# Sheet2.net
KiCad netlist of a schematic drawn in Altium Designer
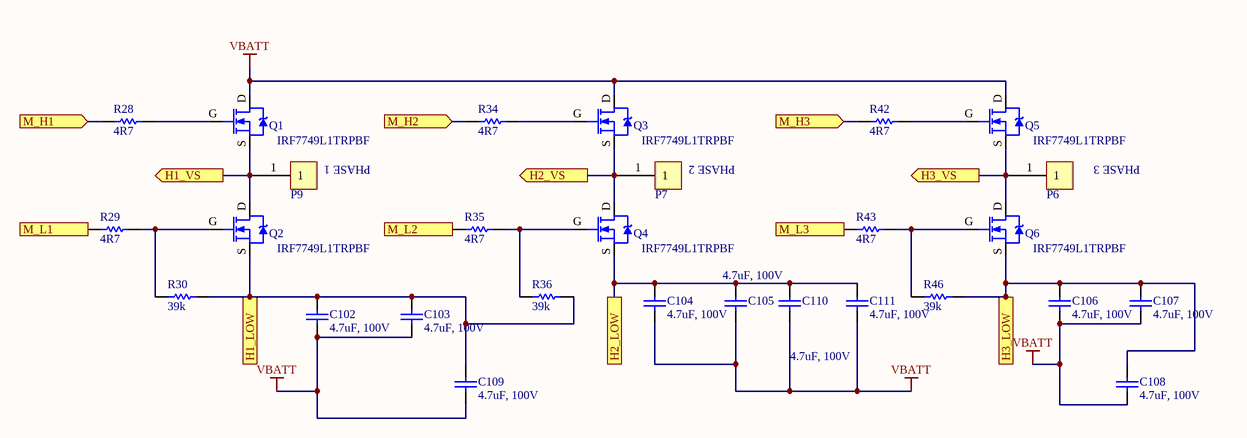
[diagram p0: Sheet2.SchDoc]

(export (version "E")
  (design (tool "Eeschema 10.0.6"))
  (components
    (comp (ref "C102")
      (value "4.7uF, 100V")
      (footprint "SMD-1206 Capacitor")
      (description "4.7µF 100V Ceramic Capacitor X7S 1206")
      (fields
        (field (name "MANUFACTURER PART NUMBER") "12061Z475MAT2A")
        (field (name "MANUFACTURER") "AVX Corporation")
      )
      (libsource (lib "Master Data Link") (part "CAP"))
    )
    (comp (ref "C103")
      (value "4.7uF, 100V")
      (footprint "SMD-1206 Capacitor")
      (description "4.7µF 100V Ceramic Capacitor X7S 1206")
      (fields
        (field (name "MANUFACTURER PART NUMBER") "12061Z475MAT2A")
        (field (name "MANUFACTURER") "AVX Corporation")
      )
      (libsource (lib "Master Data Link") (part "CAP"))
    )
    (comp (ref "C104")
      (value "4.7uF, 100V")
      (footprint "SMD-1206 Capacitor")
      (description "4.7µF 100V Ceramic Capacitor X7S 1206")
      (fields
        (field (name "MANUFACTURER PART NUMBER") "12061Z475MAT2A")
        (field (name "MANUFACTURER") "AVX Corporation")
      )
      (libsource (lib "Master Data Link") (part "CAP"))
    )
    (comp (ref "C105")
      (value "4.7uF, 100V")
      (footprint "SMD-1206 Capacitor")
      (description "4.7µF 100V Ceramic Capacitor X7S 1206")
      (fields
        (field (name "MANUFACTURER PART NUMBER") "12061Z475MAT2A")
        (field (name "MANUFACTURER") "AVX Corporation")
      )
      (libsource (lib "Master Data Link") (part "CAP"))
    )
    (comp (ref "C106")
      (value "4.7uF, 100V")
      (footprint "SMD-1206 Capacitor")
      (description "4.7µF 100V Ceramic Capacitor X7S 1206")
      (fields
        (field (name "MANUFACTURER PART NUMBER") "12061Z475MAT2A")
        (field (name "MANUFACTURER") "AVX Corporation")
      )
      (libsource (lib "Master Data Link") (part "CAP"))
    )
    (comp (ref "C107")
      (value "4.7uF, 100V")
      (footprint "SMD-1206 Capacitor")
      (description "4.7µF 100V Ceramic Capacitor X7S 1206")
      (fields
        (field (name "MANUFACTURER PART NUMBER") "12061Z475MAT2A")
        (field (name "MANUFACTURER") "AVX Corporation")
      )
      (libsource (lib "Master Data Link") (part "CAP"))
    )
    (comp (ref "C108")
      (value "4.7uF, 100V")
      (footprint "SMD-1206 Capacitor")
      (description "4.7µF 100V Ceramic Capacitor X7S 1206")
      (fields
        (field (name "MANUFACTURER PART NUMBER") "12061Z475MAT2A")
        (field (name "MANUFACTURER") "AVX Corporation")
      )
      (libsource (lib "Master Data Link") (part "CAP"))
    )
    (comp (ref "C109")
      (value "4.7uF, 100V")
      (footprint "SMD-1206 Capacitor")
      (description "4.7µF 100V Ceramic Capacitor X7S 1206")
      (fields
        (field (name "MANUFACTURER PART NUMBER") "12061Z475MAT2A")
        (field (name "MANUFACTURER") "AVX Corporation")
      )
      (libsource (lib "Master Data Link") (part "CAP"))
    )
    (comp (ref "C110")
      (value "4.7uF, 100V")
      (footprint "SMD-1206 Capacitor")
      (description "4.7µF 100V Ceramic Capacitor X7S 1206")
      (fields
        (field (name "MANUFACTURER PART NUMBER") "12061Z475MAT2A")
        (field (name "MANUFACTURER") "AVX Corporation")
      )
      (libsource (lib "Master Data Link") (part "CAP"))
    )
    (comp (ref "C111")
      (value "4.7uF, 100V")
      (footprint "SMD-1206 Capacitor")
      (description "4.7µF 100V Ceramic Capacitor X7S 1206")
      (fields
        (field (name "MANUFACTURER PART NUMBER") "12061Z475MAT2A")
        (field (name "MANUFACTURER") "AVX Corporation")
      )
      (libsource (lib "Master Data Link") (part "CAP"))
    )
    (comp (ref "P6")
      (value "-")
      (footprint "PAD1")
      (description "SMD Power landing")
      (libsource (lib "Master Data Link") (part "CON1"))
    )
    (comp (ref "P7")
      (value "-")
      (footprint "PAD1")
      (description "SMD Power landing")
      (libsource (lib "Master Data Link") (part "CON1"))
    )
    (comp (ref "P9")
      (value "-")
      (footprint "PAD1")
      (description "SMD Power landing")
      (libsource (lib "Master Data Link") (part "CON1"))
    )
    (comp (ref "Q1")
      (value "MOSFET_N")
      (footprint "DIRECTFET_1")
      (description "MOSFET N-CH 60V 200A DIRECTFETL8")
      (fields
        (field (name "MANUFACTURER PART NUMBER") "IRF7749L1TRPBF")
        (field (name "MANUFACTURER") "Infineon Technologies Americas Corp")
      )
      (libsource (lib "Master Data Link") (part "MOSFET_N"))
    )
    (comp (ref "Q2")
      (value "MOSFET_N")
      (footprint "DIRECTFET_1")
      (description "MOSFET N-CH 60V 200A DIRECTFETL8")
      (fields
        (field (name "MANUFACTURER PART NUMBER") "IRF7749L1TRPBF")
        (field (name "MANUFACTURER") "Infineon Technologies Americas Corp")
      )
      (libsource (lib "Master Data Link") (part "MOSFET_N"))
    )
    (comp (ref "Q3")
      (value "MOSFET_N")
      (footprint "DIRECTFET_1")
      (description "MOSFET N-CH 60V 200A DIRECTFETL8")
      (fields
        (field (name "MANUFACTURER PART NUMBER") "IRF7749L1TRPBF")
        (field (name "MANUFACTURER") "Infineon Technologies Americas Corp")
      )
      (libsource (lib "Master Data Link") (part "MOSFET_N"))
    )
    (comp (ref "Q4")
      (value "MOSFET_N")
      (footprint "DIRECTFET_1")
      (description "MOSFET N-CH 60V 200A DIRECTFETL8")
      (fields
        (field (name "MANUFACTURER PART NUMBER") "IRF7749L1TRPBF")
        (field (name "MANUFACTURER") "Infineon Technologies Americas Corp")
      )
      (libsource (lib "Master Data Link") (part "MOSFET_N"))
    )
    (comp (ref "Q5")
      (value "MOSFET_N")
      (footprint "DIRECTFET_1")
      (description "MOSFET N-CH 60V 200A DIRECTFETL8")
      (fields
        (field (name "MANUFACTURER PART NUMBER") "IRF7749L1TRPBF")
        (field (name "MANUFACTURER") "Infineon Technologies Americas Corp")
      )
      (libsource (lib "Master Data Link") (part "MOSFET_N"))
    )
    (comp (ref "Q6")
      (value "MOSFET_N")
      (footprint "DIRECTFET_1")
      (description "MOSFET N-CH 60V 200A DIRECTFETL8")
      (fields
        (field (name "MANUFACTURER PART NUMBER") "IRF7749L1TRPBF")
        (field (name "MANUFACTURER") "Infineon Technologies Americas Corp")
      )
      (libsource (lib "Master Data Link") (part "MOSFET_N"))
    )
    (comp (ref "R28")
      (value "4R7")
      (footprint "SMD-0603 Resistor")
      (description "R 4.7ohm, 0603")
      (fields
        (field (name "MANUFACTURER PART NUMBER") "RK73H1JTTD4R70F")
        (field (name "MANUFACTURER") "KOA Speer")
      )
      (libsource (lib "Master Data Link") (part "RES"))
    )
    (comp (ref "R29")
      (value "4R7")
      (footprint "SMD-0603 Resistor")
      (description "R 4.7ohm, 0603")
      (fields
        (field (name "MANUFACTURER PART NUMBER") "RK73H1JTTD4R70F")
        (field (name "MANUFACTURER") "KOA Speer")
      )
      (libsource (lib "Master Data Link") (part "RES"))
    )
    (comp (ref "R30")
      (value "39k")
      (footprint "SMD-0603 Resistor")
      (description "R 39k, 0603")
      (fields
        (field (name "MANUFACTURER PART NUMBER") "ERJ-3EKF3902V")
        (field (name "MANUFACTURER") "Panasonic Electronic Components")
      )
      (libsource (lib "Master Data Link") (part "RES"))
    )
    (comp (ref "R34")
      (value "4R7")
      (footprint "SMD-0603 Resistor")
      (description "R 4.7ohm, 0603")
      (fields
        (field (name "MANUFACTURER PART NUMBER") "RK73H1JTTD4R70F")
        (field (name "MANUFACTURER") "KOA Speer")
      )
      (libsource (lib "Master Data Link") (part "RES"))
    )
    (comp (ref "R35")
      (value "4R7")
      (footprint "SMD-0603 Resistor")
      (description "R 4.7ohm, 0603")
      (fields
        (field (name "MANUFACTURER PART NUMBER") "RK73H1JTTD4R70F")
        (field (name "MANUFACTURER") "KOA Speer")
      )
      (libsource (lib "Master Data Link") (part "RES"))
    )
    (comp (ref "R36")
      (value "39k")
      (footprint "SMD-0603 Resistor")
      (description "R 39k, 0603")
      (fields
        (field (name "MANUFACTURER PART NUMBER") "ERJ-3EKF3902V")
        (field (name "MANUFACTURER") "Panasonic Electronic Components")
      )
      (libsource (lib "Master Data Link") (part "RES"))
    )
    (comp (ref "R42")
      (value "4R7")
      (footprint "SMD-0603 Resistor")
      (description "R 4.7ohm, 0603")
      (fields
        (field (name "MANUFACTURER PART NUMBER") "RK73H1JTTD4R70F")
        (field (name "MANUFACTURER") "KOA Speer")
      )
      (libsource (lib "Master Data Link") (part "RES"))
    )
    (comp (ref "R43")
      (value "4R7")
      (footprint "SMD-0603 Resistor")
      (description "R 4.7ohm, 0603")
      (fields
        (field (name "MANUFACTURER PART NUMBER") "RK73H1JTTD4R70F")
        (field (name "MANUFACTURER") "KOA Speer")
      )
      (libsource (lib "Master Data Link") (part "RES"))
    )
    (comp (ref "R46")
      (value "39k")
      (footprint "SMD-0603 Resistor")
      (description "R 39k, 0603")
      (fields
        (field (name "MANUFACTURER PART NUMBER") "ERJ-3EKF3902V")
        (field (name "MANUFACTURER") "Panasonic Electronic Components")
      )
      (libsource (lib "Master Data Link") (part "RES"))
    )
  )
  (nets
    (net (code "1") (name "/H1_LOW") (class "Default")
      (node (ref "C102") (pin "2") (pinfunction "2_2") (pintype "passive"))
      (node (ref "C103") (pin "2") (pinfunction "2_2") (pintype "passive"))
      (node (ref "C109") (pin "2") (pinfunction "2_2") (pintype "passive"))
      (node (ref "Q2") (pin "S") (pinfunction "S_S") (pintype "passive"))
      (node (ref "R30") (pin "2") (pinfunction "2_2") (pintype "passive"))
      (node (ref "R36") (pin "2") (pinfunction "2_2") (pintype "passive"))
    )
    (net (code "2") (name "/H1_VS") (class "Default")
      (node (ref "P9") (pin "1") (pinfunction "1_1") (pintype "passive"))
      (node (ref "Q1") (pin "S") (pinfunction "S_S") (pintype "passive"))
      (node (ref "Q2") (pin "D") (pinfunction "D_D") (pintype "passive"))
    )
    (net (code "3") (name "/H2_LOW") (class "Default")
      (node (ref "C104") (pin "2") (pinfunction "2_2") (pintype "passive"))
      (node (ref "C105") (pin "2") (pinfunction "2_2") (pintype "passive"))
      (node (ref "C110") (pin "2") (pinfunction "2_2") (pintype "passive"))
      (node (ref "C111") (pin "2") (pinfunction "2_2") (pintype "passive"))
      (node (ref "Q4") (pin "S") (pinfunction "S_S") (pintype "passive"))
    )
    (net (code "4") (name "/H2_VS") (class "Default")
      (node (ref "P7") (pin "1") (pinfunction "1_1") (pintype "passive"))
      (node (ref "Q3") (pin "S") (pinfunction "S_S") (pintype "passive"))
      (node (ref "Q4") (pin "D") (pinfunction "D_D") (pintype "passive"))
    )
    (net (code "5") (name "/H3_LOW") (class "Default")
      (node (ref "C106") (pin "2") (pinfunction "2_2") (pintype "passive"))
      (node (ref "C107") (pin "2") (pinfunction "2_2") (pintype "passive"))
      (node (ref "C108") (pin "2") (pinfunction "2_2") (pintype "passive"))
      (node (ref "Q6") (pin "S") (pinfunction "S_S") (pintype "passive"))
      (node (ref "R46") (pin "2") (pinfunction "2_2") (pintype "passive"))
    )
    (net (code "6") (name "/H3_VS") (class "Default")
      (node (ref "P6") (pin "1") (pinfunction "1_1") (pintype "passive"))
      (node (ref "Q5") (pin "S") (pinfunction "S_S") (pintype "passive"))
      (node (ref "Q6") (pin "D") (pinfunction "D_D") (pintype "passive"))
    )
    (net (code "7") (name "/M_H1") (class "Default")
      (node (ref "R28") (pin "1") (pinfunction "1_1") (pintype "passive"))
    )
    (net (code "8") (name "/M_H2") (class "Default")
      (node (ref "R34") (pin "1") (pinfunction "1_1") (pintype "passive"))
    )
    (net (code "9") (name "/M_H3") (class "Default")
      (node (ref "R42") (pin "1") (pinfunction "1_1") (pintype "passive"))
    )
    (net (code "10") (name "/M_L1") (class "Default")
      (node (ref "R29") (pin "1") (pinfunction "1_1") (pintype "passive"))
    )
    (net (code "11") (name "/M_L2") (class "Default")
      (node (ref "R35") (pin "1") (pinfunction "1_1") (pintype "passive"))
    )
    (net (code "12") (name "/M_L3") (class "Default")
      (node (ref "R43") (pin "1") (pinfunction "1_1") (pintype "passive"))
    )
    (net (code "13") (name "Net-(Q1-PadG)") (class "Default")
      (node (ref "Q1") (pin "G") (pinfunction "G_G") (pintype "passive"))
      (node (ref "R28") (pin "2") (pinfunction "2_2") (pintype "passive"))
    )
    (net (code "14") (name "Net-(Q2-PadG)") (class "Default")
      (node (ref "Q2") (pin "G") (pinfunction "G_G") (pintype "passive"))
      (node (ref "R29") (pin "2") (pinfunction "2_2") (pintype "passive"))
      (node (ref "R30") (pin "1") (pinfunction "1_1") (pintype "passive"))
    )
    (net (code "15") (name "Net-(Q3-PadG)") (class "Default")
      (node (ref "Q3") (pin "G") (pinfunction "G_G") (pintype "passive"))
      (node (ref "R34") (pin "2") (pinfunction "2_2") (pintype "passive"))
    )
    (net (code "16") (name "Net-(Q4-PadG)") (class "Default")
      (node (ref "Q4") (pin "G") (pinfunction "G_G") (pintype "passive"))
      (node (ref "R35") (pin "2") (pinfunction "2_2") (pintype "passive"))
      (node (ref "R36") (pin "1") (pinfunction "1_1") (pintype "passive"))
    )
    (net (code "17") (name "Net-(Q5-PadG)") (class "Default")
      (node (ref "Q5") (pin "G") (pinfunction "G_G") (pintype "passive"))
      (node (ref "R42") (pin "2") (pinfunction "2_2") (pintype "passive"))
    )
    (net (code "18") (name "Net-(Q6-PadG)") (class "Default")
      (node (ref "Q6") (pin "G") (pinfunction "G_G") (pintype "passive"))
      (node (ref "R43") (pin "2") (pinfunction "2_2") (pintype "passive"))
      (node (ref "R46") (pin "1") (pinfunction "1_1") (pintype "passive"))
    )
    (net (code "19") (name "VBATT") (class "Default")
      (node (ref "C102") (pin "1") (pinfunction "1_1") (pintype "passive"))
      (node (ref "C103") (pin "1") (pinfunction "1_1") (pintype "passive"))
      (node (ref "C104") (pin "1") (pinfunction "1_1") (pintype "passive"))
      (node (ref "C105") (pin "1") (pinfunction "1_1") (pintype "passive"))
      (node (ref "C106") (pin "1") (pinfunction "1_1") (pintype "passive"))
      (node (ref "C107") (pin "1") (pinfunction "1_1") (pintype "passive"))
      (node (ref "C108") (pin "1") (pinfunction "1_1") (pintype "passive"))
      (node (ref "C109") (pin "1") (pinfunction "1_1") (pintype "passive"))
      (node (ref "C110") (pin "1") (pinfunction "1_1") (pintype "passive"))
      (node (ref "C111") (pin "1") (pinfunction "1_1") (pintype "passive"))
      (node (ref "Q1") (pin "D") (pinfunction "D_D") (pintype "passive"))
      (node (ref "Q3") (pin "D") (pinfunction "D_D") (pintype "passive"))
      (node (ref "Q5") (pin "D") (pinfunction "D_D") (pintype "passive"))
    )
  )
)
